# icm-20948-breakout.net
KiCad netlist of a schematic drawn in EAGLE
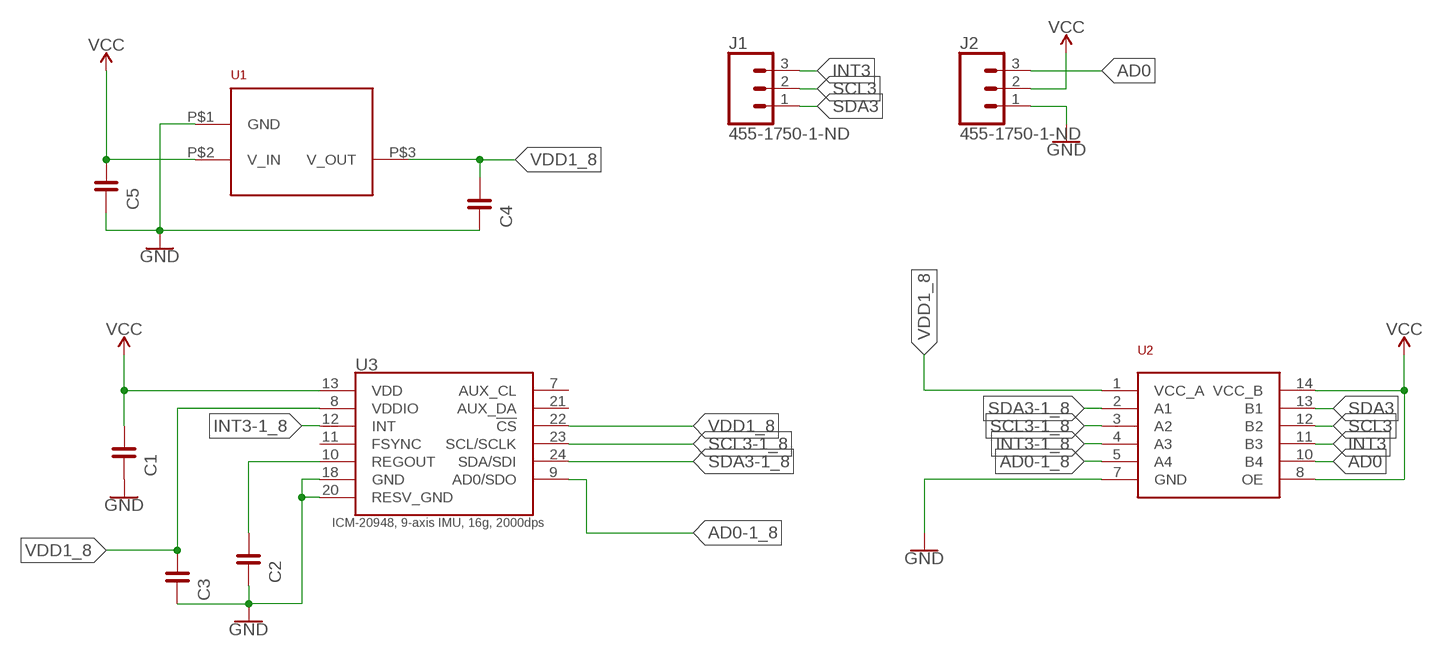
[diagram p0: schematic, sheet 1]

(export (version "E")
  (design (tool "Eeschema 10.0.6"))
  (components
    (comp (ref "C1")
      (value "0.1uF")
      (footprint "eagle-import:0402")
      (libsource (lib "eagle-import") (part "CAPACITOR-0402"))
    )
    (comp (ref "C2")
      (value "0.1uF")
      (footprint "eagle-import:0402")
      (libsource (lib "eagle-import") (part "CAPACITOR-0402"))
    )
    (comp (ref "C3")
      (value "0.1uF")
      (footprint "eagle-import:0402")
      (libsource (lib "eagle-import") (part "CAPACITOR-0402"))
    )
    (comp (ref "C4")
      (value "1.0uF")
      (footprint "eagle-import:0402")
      (libsource (lib "eagle-import") (part "CAPACITOR-0402"))
    )
    (comp (ref "C5")
      (value "1.0uF")
      (footprint "eagle-import:0402")
      (libsource (lib "eagle-import") (part "CAPACITOR-0402"))
    )
    (comp (ref "J1")
      (value "455-1750-1-ND")
      (footprint "eagle-import:1X03")
      (libsource (lib "eagle-import") (part "CONN_03"))
    )
    (comp (ref "J2")
      (value "455-1750-1-ND")
      (footprint "eagle-import:1X03")
      (libsource (lib "eagle-import") (part "CONN_03"))
    )
    (comp (ref "U1")
      (value "NCP563")
      (footprint "eagle-import:SC−82AB")
      (libsource (lib "eagle-import") (part "NCP563"))
    )
    (comp (ref "U2")
      (value "NTS0104")
      (footprint "eagle-import:SOT762-1")
      (libsource (lib "eagle-import") (part "NTS0104DHVQFN14"))
    )
    (comp (ref "U3")
      (value "ICM-20948")
      (footprint "eagle-import:SPARKFUN-SENSORS_MPU-9250")
      (libsource (lib "eagle-import") (part "ICM-20948QFN24-COARSE"))
    )
  )
  (nets
    (net (code "1") (name "AD0") (class "Default")
      (node (ref "J2") (pin "3") (pinfunction "3_3") (pintype "passive"))
      (node (ref "U2") (pin "10") (pinfunction "B4_10") (pintype "bidirectional"))
    )
    (net (code "2") (name "AD0-1_8") (class "Default")
      (node (ref "U2") (pin "5") (pinfunction "A4_5") (pintype "bidirectional"))
      (node (ref "U3") (pin "9") (pinfunction "AD0/SDO_9") (pintype "bidirectional"))
    )
    (net (code "3") (name "GND") (class "Default")
      (node (ref "C1") (pin "P$2") (pinfunction "2_P$2") (pintype "passive"))
      (node (ref "C2") (pin "P$2") (pinfunction "2_P$2") (pintype "passive"))
      (node (ref "C3") (pin "P$2") (pinfunction "2_P$2") (pintype "passive"))
      (node (ref "C4") (pin "P$2") (pinfunction "2_P$2") (pintype "passive"))
      (node (ref "C5") (pin "P$2") (pinfunction "2_P$2") (pintype "passive"))
      (node (ref "J2") (pin "1") (pinfunction "1_1") (pintype "passive"))
      (node (ref "U1") (pin "P$1") (pinfunction "GND_P$1") (pintype "bidirectional"))
      (node (ref "U2") (pin "7") (pinfunction "GND_7") (pintype "bidirectional"))
      (node (ref "U3") (pin "18") (pinfunction "GND_18") (pintype "bidirectional"))
      (node (ref "U3") (pin "20") (pinfunction "RESV_GND_20") (pintype "bidirectional"))
    )
    (net (code "4") (name "INT3") (class "Default")
      (node (ref "J1") (pin "3") (pinfunction "3_3") (pintype "passive"))
      (node (ref "U2") (pin "11") (pinfunction "B3_11") (pintype "bidirectional"))
    )
    (net (code "5") (name "INT3-1_8") (class "Default")
      (node (ref "U2") (pin "4") (pinfunction "A3_4") (pintype "bidirectional"))
      (node (ref "U3") (pin "12") (pinfunction "INT_12") (pintype "bidirectional"))
    )
    (net (code "6") (name "Net-(C2-1)") (class "Default")
      (node (ref "C2") (pin "P$1") (pinfunction "1_P$1") (pintype "passive"))
      (node (ref "U3") (pin "10") (pinfunction "REGOUT_10") (pintype "bidirectional"))
    )
    (net (code "7") (name "SCL3") (class "Default")
      (node (ref "J1") (pin "2") (pinfunction "2_2") (pintype "passive"))
      (node (ref "U2") (pin "12") (pinfunction "B2_12") (pintype "bidirectional"))
    )
    (net (code "8") (name "SCL3-1_8") (class "Default")
      (node (ref "U2") (pin "3") (pinfunction "A2_3") (pintype "bidirectional"))
      (node (ref "U3") (pin "23") (pinfunction "SCL/SCLK_23") (pintype "bidirectional"))
    )
    (net (code "9") (name "SDA3") (class "Default")
      (node (ref "J1") (pin "1") (pinfunction "1_1") (pintype "passive"))
      (node (ref "U2") (pin "13") (pinfunction "B1_13") (pintype "bidirectional"))
    )
    (net (code "10") (name "SDA3-1_8") (class "Default")
      (node (ref "U2") (pin "2") (pinfunction "A1_2") (pintype "bidirectional"))
      (node (ref "U3") (pin "24") (pinfunction "SDA/SDI_24") (pintype "bidirectional"))
    )
    (net (code "11") (name "VCC") (class "Default")
      (node (ref "C1") (pin "P$1") (pinfunction "1_P$1") (pintype "passive"))
      (node (ref "C5") (pin "P$1") (pinfunction "1_P$1") (pintype "passive"))
      (node (ref "J2") (pin "2") (pinfunction "2_2") (pintype "passive"))
      (node (ref "U1") (pin "P$2") (pinfunction "V_IN_P$2") (pintype "bidirectional"))
      (node (ref "U2") (pin "14") (pinfunction "VCC_B_14") (pintype "bidirectional"))
      (node (ref "U2") (pin "8") (pinfunction "OE_8") (pintype "bidirectional"))
      (node (ref "U3") (pin "13") (pinfunction "VDD_13") (pintype "bidirectional"))
    )
    (net (code "12") (name "VDD1_8") (class "Default")
      (node (ref "C3") (pin "P$1") (pinfunction "1_P$1") (pintype "passive"))
      (node (ref "C4") (pin "P$1") (pinfunction "1_P$1") (pintype "passive"))
      (node (ref "U1") (pin "P$3") (pinfunction "V_OUT_P$3") (pintype "bidirectional"))
      (node (ref "U2") (pin "1") (pinfunction "VCC_A_1") (pintype "bidirectional"))
      (node (ref "U3") (pin "22") (pinfunction "~{CS}_22") (pintype "bidirectional"))
      (node (ref "U3") (pin "8") (pinfunction "VDDIO_8") (pintype "bidirectional"))
    )
    (net (code "13") (name "unconnected-(U3-AUX_CL-Pad7)") (class "Default")
      (node (ref "U3") (pin "7") (pinfunction "AUX_CL_7") (pintype "bidirectional"))
    )
    (net (code "14") (name "unconnected-(U3-AUX_DA-Pad21)") (class "Default")
      (node (ref "U3") (pin "21") (pinfunction "AUX_DA_21") (pintype "bidirectional"))
    )
    (net (code "15") (name "unconnected-(U3-FSYNC-Pad11)") (class "Default")
      (node (ref "U3") (pin "11") (pinfunction "FSYNC_11") (pintype "bidirectional"))
    )
  )
)
